# LED_ATtiny85.net
KiCad netlist of a schematic drawn in EAGLE
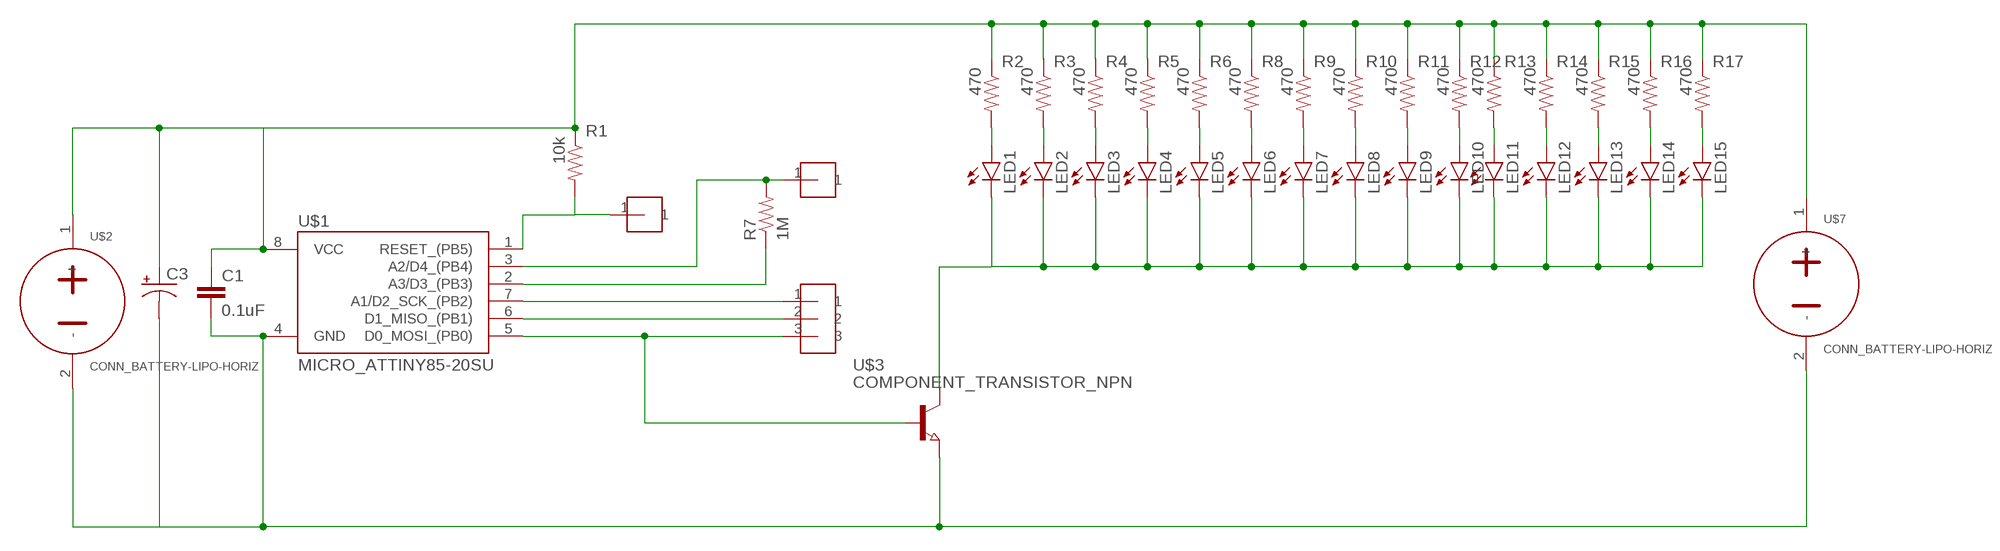
[diagram p0: schematic, sheet 1]

(export (version "E")
  (design (tool "Eeschema 10.0.6"))
  (components
    (comp (ref "C1")
      (value "0.1uF")
      (footprint "eagle-import:0805")
      (libsource (lib "eagle-import") (part "COMPONENT_CAP-0805"))
    )
    (comp (ref "C3")
      (value "COMPONENT_CAP_POL-6.3MM")
      (footprint "eagle-import:CAP_RADIAL_CAN_10MM")
      (libsource (lib "eagle-import") (part "COMPONENT_CAP_POL-6.3MM"))
    )
    (comp (ref "LED1")
      (value "LED-0805")
      (footprint "eagle-import:CHIP-LED0805")
      (libsource (lib "eagle-import") (part "LED-0805"))
    )
    (comp (ref "LED2")
      (value "LED-0805")
      (footprint "eagle-import:CHIP-LED0805")
      (libsource (lib "eagle-import") (part "LED-0805"))
    )
    (comp (ref "LED3")
      (value "LED-0805")
      (footprint "eagle-import:CHIP-LED0805")
      (libsource (lib "eagle-import") (part "LED-0805"))
    )
    (comp (ref "LED4")
      (value "LED-0805")
      (footprint "eagle-import:CHIP-LED0805")
      (libsource (lib "eagle-import") (part "LED-0805"))
    )
    (comp (ref "LED5")
      (value "LED-0805")
      (footprint "eagle-import:CHIP-LED0805")
      (libsource (lib "eagle-import") (part "LED-0805"))
    )
    (comp (ref "LED6")
      (value "LED-0805")
      (footprint "eagle-import:CHIP-LED0805")
      (libsource (lib "eagle-import") (part "LED-0805"))
    )
    (comp (ref "LED7")
      (value "LED-0805")
      (footprint "eagle-import:CHIP-LED0805")
      (libsource (lib "eagle-import") (part "LED-0805"))
    )
    (comp (ref "LED8")
      (value "LED-0805")
      (footprint "eagle-import:CHIP-LED0805")
      (libsource (lib "eagle-import") (part "LED-0805"))
    )
    (comp (ref "LED9")
      (value "LED-0805")
      (footprint "eagle-import:CHIP-LED0805")
      (libsource (lib "eagle-import") (part "LED-0805"))
    )
    (comp (ref "LED10")
      (value "LED-0805")
      (footprint "eagle-import:CHIP-LED0805")
      (libsource (lib "eagle-import") (part "LED-0805"))
    )
    (comp (ref "LED11")
      (value "LED-0805")
      (footprint "eagle-import:CHIP-LED0805")
      (libsource (lib "eagle-import") (part "LED-0805"))
    )
    (comp (ref "LED12")
      (value "LED-0805")
      (footprint "eagle-import:CHIP-LED0805")
      (libsource (lib "eagle-import") (part "LED-0805"))
    )
    (comp (ref "LED13")
      (value "LED-0805")
      (footprint "eagle-import:CHIP-LED0805")
      (libsource (lib "eagle-import") (part "LED-0805"))
    )
    (comp (ref "LED14")
      (value "LED-0805")
      (footprint "eagle-import:CHIP-LED0805")
      (libsource (lib "eagle-import") (part "LED-0805"))
    )
    (comp (ref "LED15")
      (value "LED-0805")
      (footprint "eagle-import:CHIP-LED0805")
      (libsource (lib "eagle-import") (part "LED-0805"))
    )
    (comp (ref "R1")
      (value "10k")
      (footprint "eagle-import:0805")
      (libsource (lib "eagle-import") (part "COMPONENT_RESISTOR-0805"))
    )
    (comp (ref "R2")
      (value "470")
      (footprint "eagle-import:0805")
      (libsource (lib "eagle-import") (part "COMPONENT_RESISTOR-0805"))
    )
    (comp (ref "R3")
      (value "470")
      (footprint "eagle-import:0805")
      (libsource (lib "eagle-import") (part "COMPONENT_RESISTOR-0805"))
    )
    (comp (ref "R4")
      (value "470")
      (footprint "eagle-import:0805")
      (libsource (lib "eagle-import") (part "COMPONENT_RESISTOR-0805"))
    )
    (comp (ref "R5")
      (value "470")
      (footprint "eagle-import:0805")
      (libsource (lib "eagle-import") (part "COMPONENT_RESISTOR-0805"))
    )
    (comp (ref "R6")
      (value "470")
      (footprint "eagle-import:0805")
      (libsource (lib "eagle-import") (part "COMPONENT_RESISTOR-0805"))
    )
    (comp (ref "R7")
      (value "1M")
      (footprint "eagle-import:0805")
      (libsource (lib "eagle-import") (part "COMPONENT_RESISTOR-0805"))
    )
    (comp (ref "R8")
      (value "470")
      (footprint "eagle-import:0805")
      (libsource (lib "eagle-import") (part "COMPONENT_RESISTOR-0805"))
    )
    (comp (ref "R9")
      (value "470")
      (footprint "eagle-import:0805")
      (libsource (lib "eagle-import") (part "COMPONENT_RESISTOR-0805"))
    )
    (comp (ref "R10")
      (value "470")
      (footprint "eagle-import:0805")
      (libsource (lib "eagle-import") (part "COMPONENT_RESISTOR-0805"))
    )
    (comp (ref "R11")
      (value "470")
      (footprint "eagle-import:0805")
      (libsource (lib "eagle-import") (part "COMPONENT_RESISTOR-0805"))
    )
    (comp (ref "R12")
      (value "470")
      (footprint "eagle-import:0805")
      (libsource (lib "eagle-import") (part "COMPONENT_RESISTOR-0805"))
    )
    (comp (ref "R13")
      (value "470")
      (footprint "eagle-import:0805")
      (libsource (lib "eagle-import") (part "COMPONENT_RESISTOR-0805"))
    )
    (comp (ref "R14")
      (value "470")
      (footprint "eagle-import:0805")
      (libsource (lib "eagle-import") (part "COMPONENT_RESISTOR-0805"))
    )
    (comp (ref "R15")
      (value "470")
      (footprint "eagle-import:0805")
      (libsource (lib "eagle-import") (part "COMPONENT_RESISTOR-0805"))
    )
    (comp (ref "R16")
      (value "470")
      (footprint "eagle-import:0805")
      (libsource (lib "eagle-import") (part "COMPONENT_RESISTOR-0805"))
    )
    (comp (ref "R17")
      (value "470")
      (footprint "eagle-import:0805")
      (libsource (lib "eagle-import") (part "COMPONENT_RESISTOR-0805"))
    )
    (comp (ref "U$1")
      (value "MICRO_ATTINY85-20SU")
      (footprint "eagle-import:SOIC8")
      (libsource (lib "eagle-import") (part "MICRO_ATTINY85-20SU"))
    )
    (comp (ref "U$2")
      (value "CONN_BATTERY-LIPO-HORIZ")
      (footprint "eagle-import:JST-PH-2-SMT-RA")
      (libsource (lib "eagle-import") (part "CONN_BATTERY-LIPO-HORIZ"))
    )
    (comp (ref "U$3")
      (value "COMPONENT_TRANSISTOR_NPN")
      (footprint "eagle-import:SOT23")
      (libsource (lib "eagle-import") (part "COMPONENT_TRANSISTOR_NPN"))
    )
    (comp (ref "U$4")
      (value "HEADER-1-TESTPOINT")
      (footprint "eagle-import:TESTPOINT-1")
      (libsource (lib "eagle-import") (part "HEADER-1-TESTPOINT"))
    )
    (comp (ref "U$5")
      (value "HEADER-1-TESTPOINT")
      (footprint "eagle-import:TESTPOINT-1")
      (libsource (lib "eagle-import") (part "HEADER-1-TESTPOINT"))
    )
    (comp (ref "U$6")
      (value "HEADER-3-TESTPOINT")
      (footprint "eagle-import:TESTPOINT-3")
      (libsource (lib "eagle-import") (part "HEADER-3-TESTPOINT"))
    )
    (comp (ref "U$7")
      (value "CONN_BATTERY-LIPO-HORIZ")
      (footprint "eagle-import:JST-PH-2-SMT-RA")
      (libsource (lib "eagle-import") (part "CONN_BATTERY-LIPO-HORIZ"))
    )
  )
  (nets
    (net (code "1") (name "Net-(LED1-PadA)") (class "Default")
      (node (ref "LED1") (pin "A") (pinfunction "A_A") (pintype "passive"))
      (node (ref "R2") (pin "2") (pinfunction "2_2") (pintype "passive"))
    )
    (net (code "2") (name "Net-(LED2-PadA)") (class "Default")
      (node (ref "LED2") (pin "A") (pinfunction "A_A") (pintype "passive"))
      (node (ref "R3") (pin "2") (pinfunction "2_2") (pintype "passive"))
    )
    (net (code "3") (name "Net-(LED3-PadA)") (class "Default")
      (node (ref "LED3") (pin "A") (pinfunction "A_A") (pintype "passive"))
      (node (ref "R4") (pin "2") (pinfunction "2_2") (pintype "passive"))
    )
    (net (code "4") (name "Net-(LED4-PadA)") (class "Default")
      (node (ref "LED4") (pin "A") (pinfunction "A_A") (pintype "passive"))
      (node (ref "R5") (pin "2") (pinfunction "2_2") (pintype "passive"))
    )
    (net (code "5") (name "Net-(LED5-PadA)") (class "Default")
      (node (ref "LED5") (pin "A") (pinfunction "A_A") (pintype "passive"))
      (node (ref "R6") (pin "2") (pinfunction "2_2") (pintype "passive"))
    )
    (net (code "6") (name "Net-(LED6-PadA)") (class "Default")
      (node (ref "LED6") (pin "A") (pinfunction "A_A") (pintype "passive"))
      (node (ref "R8") (pin "2") (pinfunction "2_2") (pintype "passive"))
    )
    (net (code "7") (name "Net-(LED7-PadA)") (class "Default")
      (node (ref "LED7") (pin "A") (pinfunction "A_A") (pintype "passive"))
      (node (ref "R9") (pin "2") (pinfunction "2_2") (pintype "passive"))
    )
    (net (code "8") (name "Net-(LED8-PadA)") (class "Default")
      (node (ref "LED8") (pin "A") (pinfunction "A_A") (pintype "passive"))
      (node (ref "R10") (pin "2") (pinfunction "2_2") (pintype "passive"))
    )
    (net (code "9") (name "Net-(LED9-PadA)") (class "Default")
      (node (ref "LED9") (pin "A") (pinfunction "A_A") (pintype "passive"))
      (node (ref "R11") (pin "2") (pinfunction "2_2") (pintype "passive"))
    )
    (net (code "10") (name "Net-(LED10-PadA)") (class "Default")
      (node (ref "LED10") (pin "A") (pinfunction "A_A") (pintype "passive"))
      (node (ref "R12") (pin "2") (pinfunction "2_2") (pintype "passive"))
    )
    (net (code "11") (name "Net-(LED11-PadA)") (class "Default")
      (node (ref "LED11") (pin "A") (pinfunction "A_A") (pintype "passive"))
      (node (ref "R13") (pin "2") (pinfunction "2_2") (pintype "passive"))
    )
    (net (code "12") (name "Net-(LED12-PadA)") (class "Default")
      (node (ref "LED12") (pin "A") (pinfunction "A_A") (pintype "passive"))
      (node (ref "R14") (pin "2") (pinfunction "2_2") (pintype "passive"))
    )
    (net (code "13") (name "Net-(LED13-PadA)") (class "Default")
      (node (ref "LED13") (pin "A") (pinfunction "A_A") (pintype "passive"))
      (node (ref "R15") (pin "2") (pinfunction "2_2") (pintype "passive"))
    )
    (net (code "14") (name "Net-(LED14-PadA)") (class "Default")
      (node (ref "LED14") (pin "A") (pinfunction "A_A") (pintype "passive"))
      (node (ref "R16") (pin "2") (pinfunction "2_2") (pintype "passive"))
    )
    (net (code "15") (name "Net-(LED15-PadA)") (class "Default")
      (node (ref "LED15") (pin "A") (pinfunction "A_A") (pintype "passive"))
      (node (ref "R17") (pin "2") (pinfunction "2_2") (pintype "passive"))
    )
    (net (code "16") (name "Net-(U$1-A1{slash}D2_SCK_(PB2))") (class "Default")
      (node (ref "U$1") (pin "7") (pinfunction "A1/D2_SCK_(PB2)_7") (pintype "bidirectional"))
      (node (ref "U$6") (pin "1") (pinfunction "1_1") (pintype "bidirectional"))
    )
    (net (code "17") (name "Net-(U$1-A2{slash}D4_(PB4))") (class "Default")
      (node (ref "R7") (pin "2") (pinfunction "2_2") (pintype "passive"))
      (node (ref "U$1") (pin "3") (pinfunction "A2/D4_(PB4)_3") (pintype "bidirectional"))
      (node (ref "U$4") (pin "1") (pinfunction "1_1") (pintype "bidirectional"))
    )
    (net (code "18") (name "Net-(U$1-A3{slash}D3_(PB3))") (class "Default")
      (node (ref "R7") (pin "1") (pinfunction "1_1") (pintype "passive"))
      (node (ref "U$1") (pin "2") (pinfunction "A3/D3_(PB3)_2") (pintype "bidirectional"))
    )
    (net (code "19") (name "Net-(U$1-D0_MOSI_(PB0))") (class "Default")
      (node (ref "U$1") (pin "5") (pinfunction "D0_MOSI_(PB0)_5") (pintype "bidirectional"))
      (node (ref "U$3") (pin "1") (pinfunction "B_1") (pintype "passive"))
      (node (ref "U$6") (pin "3") (pinfunction "3_3") (pintype "bidirectional"))
    )
    (net (code "20") (name "Net-(U$1-D1_MISO_(PB1))") (class "Default")
      (node (ref "U$1") (pin "6") (pinfunction "D1_MISO_(PB1)_6") (pintype "bidirectional"))
      (node (ref "U$6") (pin "2") (pinfunction "2_2") (pintype "bidirectional"))
    )
    (net (code "21") (name "Net-(U$1-GND)") (class "Default")
      (node (ref "C1") (pin "2") (pinfunction "2_2") (pintype "passive"))
      (node (ref "C3") (pin "-") (pinfunction "-_-") (pintype "passive"))
      (node (ref "U$1") (pin "4") (pinfunction "GND_4") (pintype "power_in"))
      (node (ref "U$2") (pin "2") (pinfunction "-_2") (pintype "bidirectional"))
      (node (ref "U$3") (pin "2") (pinfunction "E_2") (pintype "passive"))
      (node (ref "U$7") (pin "2") (pinfunction "-_2") (pintype "bidirectional"))
    )
    (net (code "22") (name "Net-(U$1-RESET_(PB5))") (class "Default")
      (node (ref "R1") (pin "2") (pinfunction "2_2") (pintype "passive"))
      (node (ref "U$1") (pin "1") (pinfunction "RESET_(PB5)_1") (pintype "bidirectional"))
      (node (ref "U$5") (pin "1") (pinfunction "1_1") (pintype "bidirectional"))
    )
    (net (code "23") (name "Net-(U$1-VCC)") (class "Default")
      (node (ref "C1") (pin "1") (pinfunction "1_1") (pintype "passive"))
      (node (ref "C3") (pin "+") (pinfunction "+_+") (pintype "passive"))
      (node (ref "R1") (pin "1") (pinfunction "1_1") (pintype "passive"))
      (node (ref "R10") (pin "1") (pinfunction "1_1") (pintype "passive"))
      (node (ref "R11") (pin "1") (pinfunction "1_1") (pintype "passive"))
      (node (ref "R12") (pin "1") (pinfunction "1_1") (pintype "passive"))
      (node (ref "R13") (pin "1") (pinfunction "1_1") (pintype "passive"))
      (node (ref "R14") (pin "1") (pinfunction "1_1") (pintype "passive"))
      (node (ref "R15") (pin "1") (pinfunction "1_1") (pintype "passive"))
      (node (ref "R16") (pin "1") (pinfunction "1_1") (pintype "passive"))
      (node (ref "R17") (pin "1") (pinfunction "1_1") (pintype "passive"))
      (node (ref "R2") (pin "1") (pinfunction "1_1") (pintype "passive"))
      (node (ref "R3") (pin "1") (pinfunction "1_1") (pintype "passive"))
      (node (ref "R4") (pin "1") (pinfunction "1_1") (pintype "passive"))
      (node (ref "R5") (pin "1") (pinfunction "1_1") (pintype "passive"))
      (node (ref "R6") (pin "1") (pinfunction "1_1") (pintype "passive"))
      (node (ref "R8") (pin "1") (pinfunction "1_1") (pintype "passive"))
      (node (ref "R9") (pin "1") (pinfunction "1_1") (pintype "passive"))
      (node (ref "U$1") (pin "8") (pinfunction "VCC_8") (pintype "power_in"))
      (node (ref "U$2") (pin "1") (pinfunction "+_1") (pintype "bidirectional"))
      (node (ref "U$7") (pin "1") (pinfunction "+_1") (pintype "bidirectional"))
    )
    (net (code "24") (name "Net-(U$3-C)") (class "Default")
      (node (ref "LED1") (pin "C") (pinfunction "C_C") (pintype "passive"))
      (node (ref "LED10") (pin "C") (pinfunction "C_C") (pintype "passive"))
      (node (ref "LED11") (pin "C") (pinfunction "C_C") (pintype "passive"))
      (node (ref "LED12") (pin "C") (pinfunction "C_C") (pintype "passive"))
      (node (ref "LED13") (pin "C") (pinfunction "C_C") (pintype "passive"))
      (node (ref "LED14") (pin "C") (pinfunction "C_C") (pintype "passive"))
      (node (ref "LED15") (pin "C") (pinfunction "C_C") (pintype "passive"))
      (node (ref "LED2") (pin "C") (pinfunction "C_C") (pintype "passive"))
      (node (ref "LED3") (pin "C") (pinfunction "C_C") (pintype "passive"))
      (node (ref "LED4") (pin "C") (pinfunction "C_C") (pintype "passive"))
      (node (ref "LED5") (pin "C") (pinfunction "C_C") (pintype "passive"))
      (node (ref "LED6") (pin "C") (pinfunction "C_C") (pintype "passive"))
      (node (ref "LED7") (pin "C") (pinfunction "C_C") (pintype "passive"))
      (node (ref "LED8") (pin "C") (pinfunction "C_C") (pintype "passive"))
      (node (ref "LED9") (pin "C") (pinfunction "C_C") (pintype "passive"))
      (node (ref "U$3") (pin "3") (pinfunction "C_3") (pintype "passive"))
    )
  )
)
